# dise_o_placa_pcb.net
KiCad netlist of a schematic drawn in EAGLE
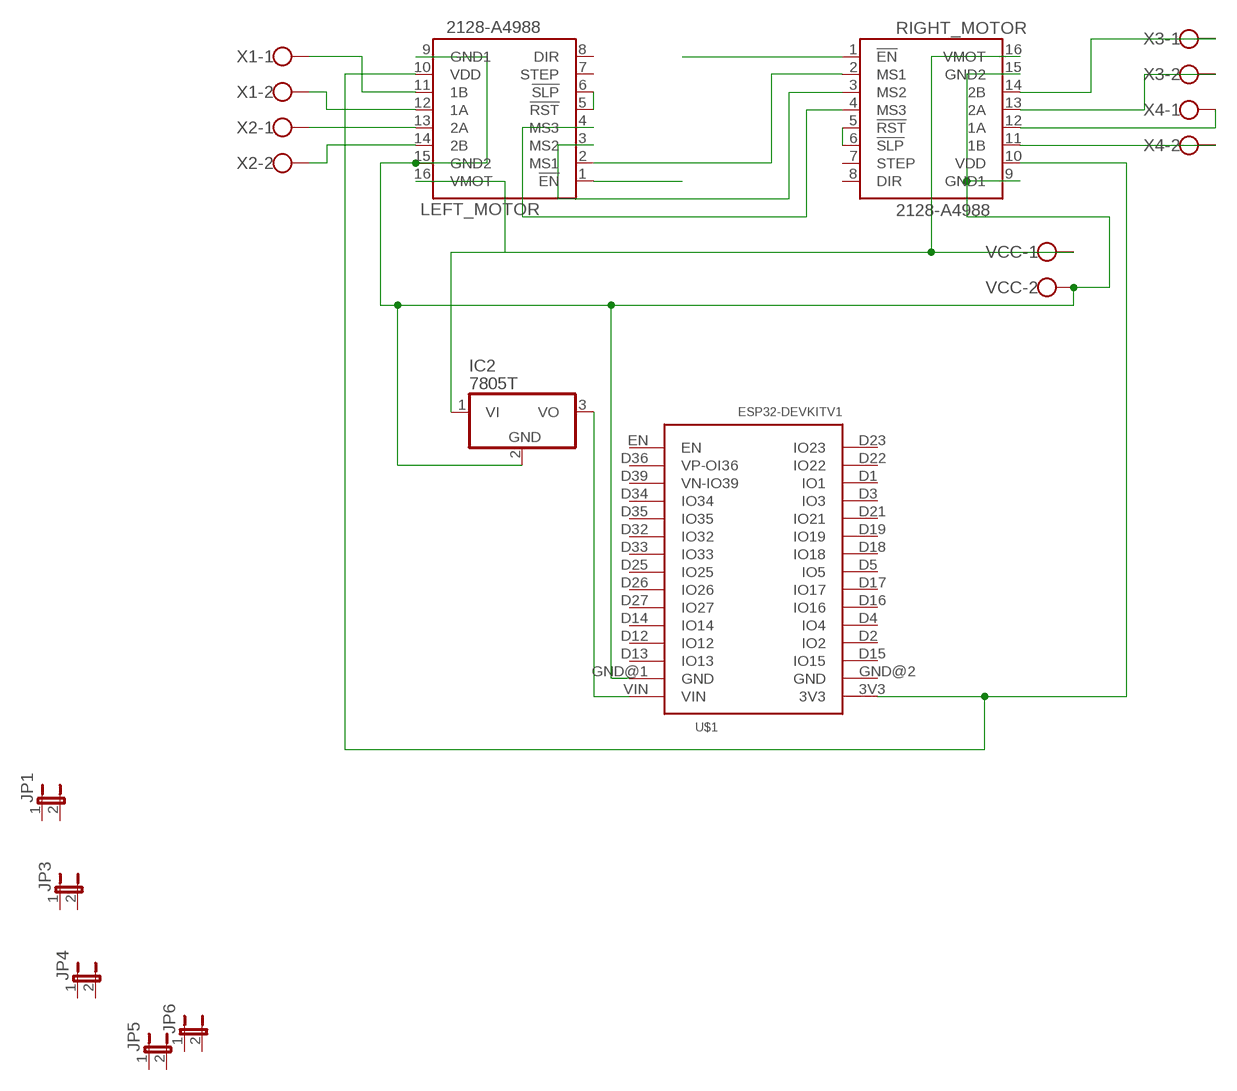
[diagram p0: schematic, sheet 1]

(export (version "E")
  (design (tool "Eeschema 10.0.6"))
  (components
    (comp (ref "IC2")
      (value "7805T")
      (footprint "eagle-import:TO220H")
      (libsource (lib "eagle-import") (part "78T05"))
    )
    (comp (ref "JP1")
      (value "JP1E")
      (footprint "eagle-import:JP1")
      (libsource (lib "eagle-import") (part "JP1E"))
    )
    (comp (ref "JP3")
      (value "JP1E")
      (footprint "eagle-import:JP1")
      (libsource (lib "eagle-import") (part "JP1E"))
    )
    (comp (ref "JP4")
      (value "JP1E")
      (footprint "eagle-import:JP1")
      (libsource (lib "eagle-import") (part "JP1E"))
    )
    (comp (ref "JP5")
      (value "JP1E")
      (footprint "eagle-import:JP1")
      (libsource (lib "eagle-import") (part "JP1E"))
    )
    (comp (ref "JP6")
      (value "JP1E")
      (footprint "eagle-import:JP1")
      (libsource (lib "eagle-import") (part "JP1E"))
    )
    (comp (ref "LEFT_MOTOR")
      (value "2128-A4988")
      (footprint "eagle-import:A4988")
      (libsource (lib "eagle-import") (part "2128-A4988"))
    )
    (comp (ref "RIGHT_MOTOR")
      (value "2128-A4988")
      (footprint "eagle-import:A4988")
      (libsource (lib "eagle-import") (part "2128-A4988"))
    )
    (comp (ref "U$1")
      (value "ESP32DEVKITV1")
      (footprint "eagle-import:ESP32-DEVKITV1")
      (libsource (lib "eagle-import") (part "ESP32DEVKITV1"))
    )
    (comp (ref "VCC")
      (value "W237-102")
      (footprint "eagle-import:W237-102")
      (fields (field (name "MPN") "237-102"))
      (libsource (lib "eagle-import") (part "W237-102"))
    )
    (comp (ref "X1")
      (value "W237-102")
      (footprint "eagle-import:W237-102")
      (fields (field (name "MPN") "237-102"))
      (libsource (lib "eagle-import") (part "W237-102"))
    )
    (comp (ref "X2")
      (value "W237-102")
      (footprint "eagle-import:W237-102")
      (fields (field (name "MPN") "237-102"))
      (libsource (lib "eagle-import") (part "W237-102"))
    )
    (comp (ref "X3")
      (value "W237-102")
      (footprint "eagle-import:W237-102")
      (fields (field (name "MPN") "237-102"))
      (libsource (lib "eagle-import") (part "W237-102"))
    )
    (comp (ref "X4")
      (value "W237-102")
      (footprint "eagle-import:W237-102")
      (fields (field (name "MPN") "237-102"))
      (libsource (lib "eagle-import") (part "W237-102"))
    )
  )
  (nets
    (net (code "1") (name "Net-(IC2-GND)") (class "Default")
      (node (ref "IC2") (pin "2") (pinfunction "GND_2") (pintype "passive"))
      (node (ref "LEFT_MOTOR") (pin "15") (pinfunction "GND2_15") (pintype "power_in"))
      (node (ref "LEFT_MOTOR") (pin "9") (pinfunction "GND1_9") (pintype "power_in"))
      (node (ref "RIGHT_MOTOR") (pin "15") (pinfunction "GND2_15") (pintype "power_in"))
      (node (ref "RIGHT_MOTOR") (pin "9") (pinfunction "GND1_9") (pintype "power_in"))
      (node (ref "U$1") (pin "GND@1") (pinfunction "GND_GND@1") (pintype "bidirectional"))
      (node (ref "VCC") (pin "2") (pinfunction "KL_2") (pintype "passive"))
    )
    (net (code "2") (name "Net-(IC2-VI)") (class "Default")
      (node (ref "IC2") (pin "1") (pinfunction "VI_1") (pintype "input"))
      (node (ref "LEFT_MOTOR") (pin "16") (pinfunction "VMOT_16") (pintype "power_in"))
      (node (ref "RIGHT_MOTOR") (pin "16") (pinfunction "VMOT_16") (pintype "power_in"))
      (node (ref "VCC") (pin "1") (pinfunction "KL_1") (pintype "passive"))
    )
    (net (code "3") (name "Net-(IC2-VO)") (class "Default")
      (node (ref "IC2") (pin "3") (pinfunction "VO_3") (pintype "passive"))
      (node (ref "U$1") (pin "VIN") (pinfunction "VIN_VIN") (pintype "bidirectional"))
    )
    (net (code "4") (name "Net-(LEFT_MOTOR-1A)") (class "Default")
      (node (ref "LEFT_MOTOR") (pin "12") (pinfunction "1A_12") (pintype "output"))
      (node (ref "X1") (pin "2") (pinfunction "KL_2") (pintype "passive"))
    )
    (net (code "5") (name "Net-(LEFT_MOTOR-1B)") (class "Default")
      (node (ref "LEFT_MOTOR") (pin "11") (pinfunction "1B_11") (pintype "output"))
      (node (ref "X1") (pin "1") (pinfunction "KL_1") (pintype "passive"))
    )
    (net (code "6") (name "Net-(LEFT_MOTOR-2A)") (class "Default")
      (node (ref "LEFT_MOTOR") (pin "13") (pinfunction "2A_13") (pintype "output"))
      (node (ref "X2") (pin "1") (pinfunction "KL_1") (pintype "passive"))
    )
    (net (code "7") (name "Net-(LEFT_MOTOR-2B)") (class "Default")
      (node (ref "LEFT_MOTOR") (pin "14") (pinfunction "2B_14") (pintype "output"))
      (node (ref "X2") (pin "2") (pinfunction "KL_2") (pintype "passive"))
    )
    (net (code "8") (name "Net-(LEFT_MOTOR-MS1)") (class "Default")
      (node (ref "LEFT_MOTOR") (pin "2") (pinfunction "MS1_2") (pintype "passive"))
      (node (ref "RIGHT_MOTOR") (pin "2") (pinfunction "MS1_2") (pintype "passive"))
    )
    (net (code "9") (name "Net-(LEFT_MOTOR-MS2)") (class "Default")
      (node (ref "LEFT_MOTOR") (pin "3") (pinfunction "MS2_3") (pintype "passive"))
      (node (ref "RIGHT_MOTOR") (pin "3") (pinfunction "MS2_3") (pintype "passive"))
    )
    (net (code "10") (name "Net-(LEFT_MOTOR-MS3)") (class "Default")
      (node (ref "LEFT_MOTOR") (pin "4") (pinfunction "MS3_4") (pintype "passive"))
      (node (ref "RIGHT_MOTOR") (pin "4") (pinfunction "MS3_4") (pintype "passive"))
    )
    (net (code "11") (name "Net-(LEFT_MOTOR-VDD)") (class "Default")
      (node (ref "LEFT_MOTOR") (pin "10") (pinfunction "VDD_10") (pintype "power_in"))
      (node (ref "RIGHT_MOTOR") (pin "10") (pinfunction "VDD_10") (pintype "power_in"))
      (node (ref "U$1") (pin "3V3") (pinfunction "3V3_3V3") (pintype "bidirectional"))
    )
    (net (code "12") (name "Net-(LEFT_MOTOR-~{RST})") (class "Default")
      (node (ref "LEFT_MOTOR") (pin "5") (pinfunction "~{RST}_5") (pintype "passive"))
      (node (ref "LEFT_MOTOR") (pin "6") (pinfunction "~{SLP}_6") (pintype "passive"))
    )
    (net (code "13") (name "Net-(RIGHT_MOTOR-1A)") (class "Default")
      (node (ref "RIGHT_MOTOR") (pin "12") (pinfunction "1A_12") (pintype "output"))
      (node (ref "X4") (pin "1") (pinfunction "KL_1") (pintype "passive"))
    )
    (net (code "14") (name "Net-(RIGHT_MOTOR-1B)") (class "Default")
      (node (ref "RIGHT_MOTOR") (pin "11") (pinfunction "1B_11") (pintype "output"))
      (node (ref "X4") (pin "2") (pinfunction "KL_2") (pintype "passive"))
    )
    (net (code "15") (name "Net-(RIGHT_MOTOR-2A)") (class "Default")
      (node (ref "RIGHT_MOTOR") (pin "13") (pinfunction "2A_13") (pintype "output"))
      (node (ref "X3") (pin "2") (pinfunction "KL_2") (pintype "passive"))
    )
    (net (code "16") (name "Net-(RIGHT_MOTOR-2B)") (class "Default")
      (node (ref "RIGHT_MOTOR") (pin "14") (pinfunction "2B_14") (pintype "output"))
      (node (ref "X3") (pin "1") (pinfunction "KL_1") (pintype "passive"))
    )
    (net (code "17") (name "Net-(RIGHT_MOTOR-~{RST})") (class "Default")
      (node (ref "RIGHT_MOTOR") (pin "5") (pinfunction "~{RST}_5") (pintype "passive"))
      (node (ref "RIGHT_MOTOR") (pin "6") (pinfunction "~{SLP}_6") (pintype "passive"))
    )
    (net (code "18") (name "unconnected-(JP1-Pad1)") (class "Default")
      (node (ref "JP1") (pin "1") (pinfunction "1_1") (pintype "passive"))
    )
    (net (code "19") (name "unconnected-(JP1-Pad2)") (class "Default")
      (node (ref "JP1") (pin "2") (pinfunction "2_2") (pintype "passive"))
    )
    (net (code "20") (name "unconnected-(JP3-Pad1)") (class "Default")
      (node (ref "JP3") (pin "1") (pinfunction "1_1") (pintype "passive"))
    )
    (net (code "21") (name "unconnected-(JP3-Pad2)") (class "Default")
      (node (ref "JP3") (pin "2") (pinfunction "2_2") (pintype "passive"))
    )
    (net (code "22") (name "unconnected-(JP4-Pad1)") (class "Default")
      (node (ref "JP4") (pin "1") (pinfunction "1_1") (pintype "passive"))
    )
    (net (code "23") (name "unconnected-(JP4-Pad2)") (class "Default")
      (node (ref "JP4") (pin "2") (pinfunction "2_2") (pintype "passive"))
    )
    (net (code "24") (name "unconnected-(JP5-Pad1)") (class "Default")
      (node (ref "JP5") (pin "1") (pinfunction "1_1") (pintype "passive"))
    )
    (net (code "25") (name "unconnected-(JP5-Pad2)") (class "Default")
      (node (ref "JP5") (pin "2") (pinfunction "2_2") (pintype "passive"))
    )
    (net (code "26") (name "unconnected-(JP6-Pad1)") (class "Default")
      (node (ref "JP6") (pin "1") (pinfunction "1_1") (pintype "passive"))
    )
    (net (code "27") (name "unconnected-(JP6-Pad2)") (class "Default")
      (node (ref "JP6") (pin "2") (pinfunction "2_2") (pintype "passive"))
    )
    (net (code "28") (name "unconnected-(LEFT_MOTOR-DIR-Pad8)") (class "Default")
      (node (ref "LEFT_MOTOR") (pin "8") (pinfunction "DIR_8") (pintype "input"))
    )
    (net (code "29") (name "unconnected-(LEFT_MOTOR-STEP-Pad7)") (class "Default")
      (node (ref "LEFT_MOTOR") (pin "7") (pinfunction "STEP_7") (pintype "input"))
    )
    (net (code "30") (name "unconnected-(LEFT_MOTOR-~{EN}-Pad1)") (class "Default")
      (node (ref "LEFT_MOTOR") (pin "1") (pinfunction "~{EN}_1") (pintype "passive"))
    )
    (net (code "31") (name "unconnected-(RIGHT_MOTOR-DIR-Pad8)") (class "Default")
      (node (ref "RIGHT_MOTOR") (pin "8") (pinfunction "DIR_8") (pintype "input"))
    )
    (net (code "32") (name "unconnected-(RIGHT_MOTOR-STEP-Pad7)") (class "Default")
      (node (ref "RIGHT_MOTOR") (pin "7") (pinfunction "STEP_7") (pintype "input"))
    )
    (net (code "33") (name "unconnected-(RIGHT_MOTOR-~{EN}-Pad1)") (class "Default")
      (node (ref "RIGHT_MOTOR") (pin "1") (pinfunction "~{EN}_1") (pintype "passive"))
    )
    (net (code "34") (name "unconnected-(U$1-GND-PadGND@2)") (class "Default")
      (node (ref "U$1") (pin "GND@2") (pinfunction "GND_GND@2") (pintype "bidirectional"))
    )
    (net (code "35") (name "unconnected-(U$1-IO1-PadD1)") (class "Default")
      (node (ref "U$1") (pin "D1") (pinfunction "IO1_D1") (pintype "bidirectional"))
    )
    (net (code "36") (name "unconnected-(U$1-IO2-PadD2)") (class "Default")
      (node (ref "U$1") (pin "D2") (pinfunction "IO2_D2") (pintype "bidirectional"))
    )
    (net (code "37") (name "unconnected-(U$1-IO3-PadD3)") (class "Default")
      (node (ref "U$1") (pin "D3") (pinfunction "IO3_D3") (pintype "bidirectional"))
    )
    (net (code "38") (name "unconnected-(U$1-IO4-PadD4)") (class "Default")
      (node (ref "U$1") (pin "D4") (pinfunction "IO4_D4") (pintype "bidirectional"))
    )
    (net (code "39") (name "unconnected-(U$1-IO5-PadD5)") (class "Default")
      (node (ref "U$1") (pin "D5") (pinfunction "IO5_D5") (pintype "bidirectional"))
    )
    (net (code "40") (name "unconnected-(U$1-IO12-PadD12)") (class "Default")
      (node (ref "U$1") (pin "D12") (pinfunction "IO12_D12") (pintype "bidirectional"))
    )
    (net (code "41") (name "unconnected-(U$1-IO13-PadD13)") (class "Default")
      (node (ref "U$1") (pin "D13") (pinfunction "IO13_D13") (pintype "bidirectional"))
    )
    (net (code "42") (name "unconnected-(U$1-IO14-PadD14)") (class "Default")
      (node (ref "U$1") (pin "D14") (pinfunction "IO14_D14") (pintype "bidirectional"))
    )
    (net (code "43") (name "unconnected-(U$1-IO15-PadD15)") (class "Default")
      (node (ref "U$1") (pin "D15") (pinfunction "IO15_D15") (pintype "bidirectional"))
    )
    (net (code "44") (name "unconnected-(U$1-IO16-PadD16)") (class "Default")
      (node (ref "U$1") (pin "D16") (pinfunction "IO16_D16") (pintype "bidirectional"))
    )
    (net (code "45") (name "unconnected-(U$1-IO17-PadD17)") (class "Default")
      (node (ref "U$1") (pin "D17") (pinfunction "IO17_D17") (pintype "bidirectional"))
    )
    (net (code "46") (name "unconnected-(U$1-IO18-PadD18)") (class "Default")
      (node (ref "U$1") (pin "D18") (pinfunction "IO18_D18") (pintype "bidirectional"))
    )
    (net (code "47") (name "unconnected-(U$1-IO19-PadD19)") (class "Default")
      (node (ref "U$1") (pin "D19") (pinfunction "IO19_D19") (pintype "bidirectional"))
    )
    (net (code "48") (name "unconnected-(U$1-IO21-PadD21)") (class "Default")
      (node (ref "U$1") (pin "D21") (pinfunction "IO21_D21") (pintype "bidirectional"))
    )
    (net (code "49") (name "unconnected-(U$1-IO22-PadD22)") (class "Default")
      (node (ref "U$1") (pin "D22") (pinfunction "IO22_D22") (pintype "bidirectional"))
    )
    (net (code "50") (name "unconnected-(U$1-IO23-PadD23)") (class "Default")
      (node (ref "U$1") (pin "D23") (pinfunction "IO23_D23") (pintype "bidirectional"))
    )
    (net (code "51") (name "unconnected-(U$1-IO25-PadD25)") (class "Default")
      (node (ref "U$1") (pin "D25") (pinfunction "IO25_D25") (pintype "bidirectional"))
    )
    (net (code "52") (name "unconnected-(U$1-IO26-PadD26)") (class "Default")
      (node (ref "U$1") (pin "D26") (pinfunction "IO26_D26") (pintype "bidirectional"))
    )
    (net (code "53") (name "unconnected-(U$1-IO27-PadD27)") (class "Default")
      (node (ref "U$1") (pin "D27") (pinfunction "IO27_D27") (pintype "bidirectional"))
    )
    (net (code "54") (name "unconnected-(U$1-IO32-PadD32)") (class "Default")
      (node (ref "U$1") (pin "D32") (pinfunction "IO32_D32") (pintype "bidirectional"))
    )
    (net (code "55") (name "unconnected-(U$1-IO33-PadD33)") (class "Default")
      (node (ref "U$1") (pin "D33") (pinfunction "IO33_D33") (pintype "bidirectional"))
    )
    (net (code "56") (name "unconnected-(U$1-IO34-PadD34)") (class "Default")
      (node (ref "U$1") (pin "D34") (pinfunction "IO34_D34") (pintype "bidirectional"))
    )
    (net (code "57") (name "unconnected-(U$1-IO35-PadD35)") (class "Default")
      (node (ref "U$1") (pin "D35") (pinfunction "IO35_D35") (pintype "bidirectional"))
    )
    (net (code "58") (name "unconnected-(U$1-PadEN)") (class "Default")
      (node (ref "U$1") (pin "EN") (pinfunction "EN_EN") (pintype "bidirectional"))
    )
    (net (code "59") (name "unconnected-(U$1-VN-IO39-PadD39)") (class "Default")
      (node (ref "U$1") (pin "D39") (pinfunction "VN-IO39_D39") (pintype "bidirectional"))
    )
    (net (code "60") (name "unconnected-(U$1-VP-OI36-PadD36)") (class "Default")
      (node (ref "U$1") (pin "D36") (pinfunction "VP-OI36_D36") (pintype "bidirectional"))
    )
  )
)
